# Super_Boost.net
KiCad netlist of a schematic drawn in EAGLE
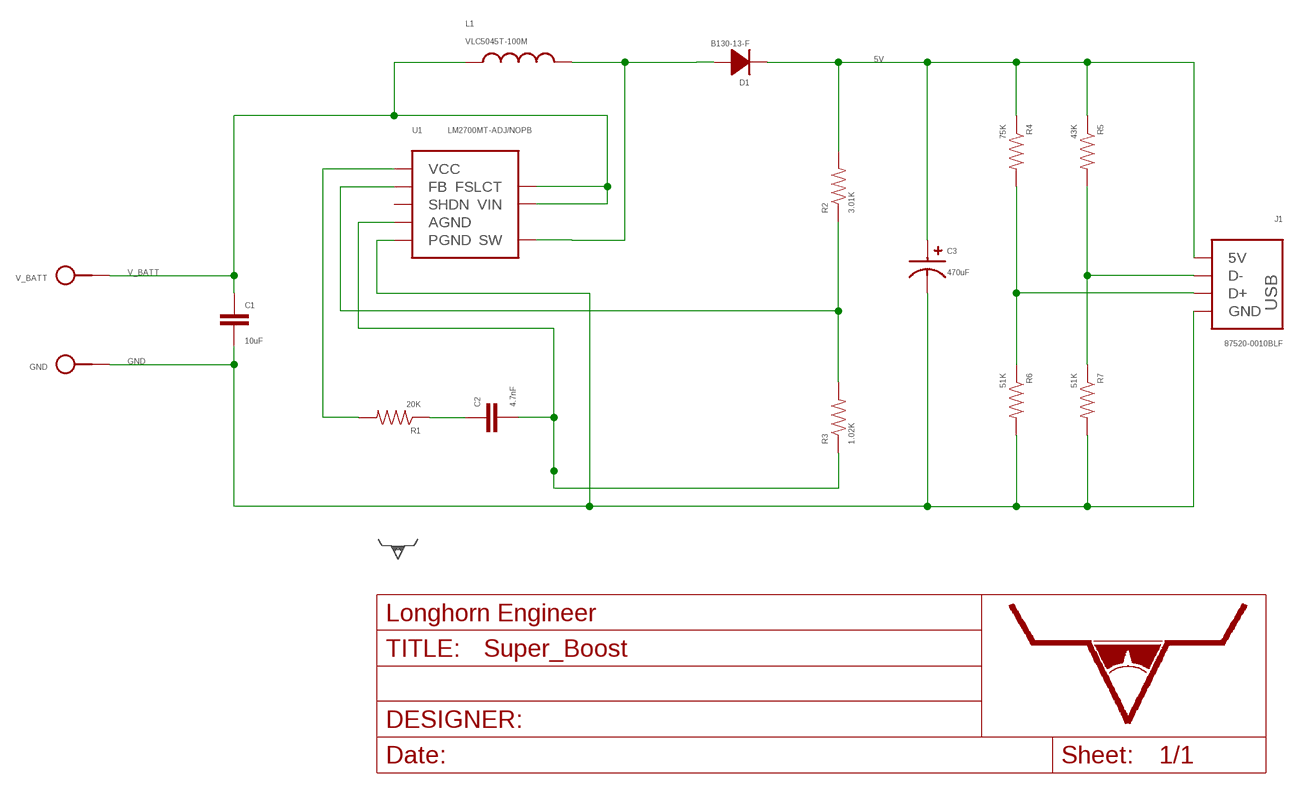
[diagram p0: schematic, sheet 1]

(export (version "E")
  (design (tool "Eeschema 10.0.6"))
  (components
    (comp (ref "C1")
      (value "10uF")
      (footprint "eagle-import:0603")
      (libsource (lib "eagle-import") (part "CAPACITOR_NON_POLAR0603"))
    )
    (comp (ref "C2")
      (value "4.7nF")
      (footprint "eagle-import:0805")
      (libsource (lib "eagle-import") (part "CAPACITOR_NON_POLAR0805"))
    )
    (comp (ref "C3")
      (value "470uF")
      (footprint "eagle-import:10MM_CAP_SMD")
      (libsource (lib "eagle-import") (part "CAPACITOR_POLARIZED10MM_SMD"))
    )
    (comp (ref "D1")
      (value "B130-13-F")
      (footprint "eagle-import:B130-13-F")
      (libsource (lib "eagle-import") (part "DIODEB130-13-F"))
    )
    (comp (ref "GND")
      (value "TEST_POINT_SINGLEKEYSTONE_5115-5119")
      (footprint "eagle-import:KEYSTONE_5115-5119")
      (libsource (lib "eagle-import") (part "TEST_POINT_SINGLEKEYSTONE_5115-5119"))
    )
    (comp (ref "J1")
      (value "87520-0010BLF")
      (footprint "eagle-import:87520-0010BLF")
      (libsource (lib "eagle-import") (part "USB_487520-0010BLF"))
    )
    (comp (ref "L1")
      (value "VLC5045T-100M")
      (footprint "eagle-import:VLC5045")
      (libsource (lib "eagle-import") (part "INDUCTORVLC5045"))
    )
    (comp (ref "R1")
      (value "20K")
      (footprint "eagle-import:0603")
      (libsource (lib "eagle-import") (part "RESISTOR0603"))
    )
    (comp (ref "R2")
      (value "3.01K")
      (footprint "eagle-import:0603")
      (libsource (lib "eagle-import") (part "RESISTOR0603"))
    )
    (comp (ref "R3")
      (value "1.02K")
      (footprint "eagle-import:0603")
      (libsource (lib "eagle-import") (part "RESISTOR0603"))
    )
    (comp (ref "R4")
      (value "75K")
      (footprint "eagle-import:0603")
      (libsource (lib "eagle-import") (part "RESISTOR0603"))
    )
    (comp (ref "R5")
      (value "43K")
      (footprint "eagle-import:0603")
      (libsource (lib "eagle-import") (part "RESISTOR0603"))
    )
    (comp (ref "R6")
      (value "51K")
      (footprint "eagle-import:0603")
      (libsource (lib "eagle-import") (part "RESISTOR0603"))
    )
    (comp (ref "R7")
      (value "51K")
      (footprint "eagle-import:0603")
      (libsource (lib "eagle-import") (part "RESISTOR0603"))
    )
    (comp (ref "U$1")
      (value "LHE_LOGO")
      (footprint "eagle-import:LHE_LOGO")
      (libsource (lib "eagle-import") (part "LHE_LOGO"))
    )
    (comp (ref "U$5")
      (value "LHE_FRAME")
      (footprint "eagle-import:LHE_FRAME")
      (fields (field (name "DNAME") "Parker Dillmann") (field (name "REVNUM") "REV 2"))
      (libsource (lib "eagle-import") (part "LHE_FRAME"))
    )
    (comp (ref "U1")
      (value "LM2700MT-ADJ/NOPB")
      (footprint "eagle-import:TSSOP-14")
      (libsource (lib "eagle-import") (part "LM2700TSSOP-14"))
    )
    (comp (ref "V_BATT")
      (value "TEST_POINT_SINGLEKEYSTONE_5115-5119")
      (footprint "eagle-import:KEYSTONE_5115-5119")
      (libsource (lib "eagle-import") (part "TEST_POINT_SINGLEKEYSTONE_5115-5119"))
    )
  )
  (nets
    (net (code "1") (name "/5V") (class "Default")
      (node (ref "C3") (pin "POS") (pinfunction "POS_POS") (pintype "bidirectional"))
      (node (ref "D1") (pin "CATHODE") (pinfunction "CATHODE_CATHODE") (pintype "bidirectional"))
      (node (ref "J1") (pin "5V") (pinfunction "5V_5V") (pintype "bidirectional"))
      (node (ref "R2") (pin "2") (pinfunction "2_2") (pintype "passive"))
      (node (ref "R4") (pin "1") (pinfunction "1_1") (pintype "passive"))
      (node (ref "R5") (pin "1") (pinfunction "1_1") (pintype "passive"))
    )
    (net (code "2") (name "/GND") (class "Default")
      (node (ref "C1") (pin "2") (pinfunction "2_2") (pintype "passive"))
      (node (ref "C3") (pin "NEG") (pinfunction "NEG_NEG") (pintype "bidirectional"))
      (node (ref "GND") (pin "P$1") (pinfunction "P$1_P$1") (pintype "bidirectional"))
      (node (ref "J1") (pin "GND") (pinfunction "GND_GND") (pintype "bidirectional"))
      (node (ref "J1") (pin "SHLD0") (pinfunction "GND_SHLD0") (pintype "bidirectional"))
      (node (ref "J1") (pin "SHLD1") (pinfunction "GND_SHLD1") (pintype "bidirectional"))
      (node (ref "R6") (pin "2") (pinfunction "2_2") (pintype "passive"))
      (node (ref "R7") (pin "2") (pinfunction "2_2") (pintype "passive"))
      (node (ref "U1") (pin "5") (pinfunction "PGND_5") (pintype "bidirectional"))
      (node (ref "U1") (pin "6") (pinfunction "PGND_6") (pintype "bidirectional"))
      (node (ref "U1") (pin "7") (pinfunction "PGND_7") (pintype "bidirectional"))
    )
    (net (code "3") (name "/V_BATT") (class "Default")
      (node (ref "C1") (pin "1") (pinfunction "1_1") (pintype "passive"))
      (node (ref "L1") (pin "P$1") (pinfunction "P$1_P$1") (pintype "bidirectional"))
      (node (ref "U1") (pin "12") (pinfunction "VIN_12") (pintype "bidirectional"))
      (node (ref "U1") (pin "13") (pinfunction "FSLCT_13") (pintype "bidirectional"))
      (node (ref "V_BATT") (pin "P$1") (pinfunction "P$1_P$1") (pintype "bidirectional"))
    )
    (net (code "4") (name "Net-(C2-Pad1)") (class "Default")
      (node (ref "C2") (pin "1") (pinfunction "1_1") (pintype "passive"))
      (node (ref "R1") (pin "1") (pinfunction "1_1") (pintype "passive"))
    )
    (net (code "5") (name "Net-(D1-PadANODE)") (class "Default")
      (node (ref "D1") (pin "ANODE") (pinfunction "ANODE_ANODE") (pintype "bidirectional"))
      (node (ref "L1") (pin "P$2") (pinfunction "P$2_P$2") (pintype "bidirectional"))
      (node (ref "U1") (pin "10") (pinfunction "SW_10") (pintype "bidirectional"))
      (node (ref "U1") (pin "8") (pinfunction "SW_8") (pintype "bidirectional"))
      (node (ref "U1") (pin "9") (pinfunction "SW_9") (pintype "bidirectional"))
    )
    (net (code "6") (name "Net-(J1-PadD+)") (class "Default")
      (node (ref "J1") (pin "D+") (pinfunction "D+_D+") (pintype "bidirectional"))
      (node (ref "R4") (pin "2") (pinfunction "2_2") (pintype "passive"))
      (node (ref "R6") (pin "1") (pinfunction "1_1") (pintype "passive"))
    )
    (net (code "7") (name "Net-(J1-PadD-)") (class "Default")
      (node (ref "J1") (pin "D-") (pinfunction "D-_D-") (pintype "bidirectional"))
      (node (ref "R5") (pin "2") (pinfunction "2_2") (pintype "passive"))
      (node (ref "R7") (pin "1") (pinfunction "1_1") (pintype "passive"))
    )
    (net (code "8") (name "Net-(U1-AGND)") (class "Default")
      (node (ref "C2") (pin "2") (pinfunction "2_2") (pintype "passive"))
      (node (ref "R3") (pin "1") (pinfunction "1_1") (pintype "passive"))
      (node (ref "U1") (pin "4") (pinfunction "AGND_4") (pintype "bidirectional"))
    )
    (net (code "9") (name "Net-(U1-FB)") (class "Default")
      (node (ref "R2") (pin "1") (pinfunction "1_1") (pintype "passive"))
      (node (ref "R3") (pin "2") (pinfunction "2_2") (pintype "passive"))
      (node (ref "U1") (pin "2") (pinfunction "FB_2") (pintype "bidirectional"))
    )
    (net (code "10") (name "Net-(U1-VCC)") (class "Default")
      (node (ref "R1") (pin "2") (pinfunction "2_2") (pintype "passive"))
      (node (ref "U1") (pin "1") (pinfunction "VCC_1") (pintype "bidirectional"))
    )
    (net (code "11") (name "unconnected-(U1-SHDN-Pad3)") (class "Default")
      (node (ref "U1") (pin "3") (pinfunction "SHDN_3") (pintype "bidirectional"))
    )
  )
)
